# USB_SWITCH_B.net
KiCad netlist of a schematic drawn in Altium Designer
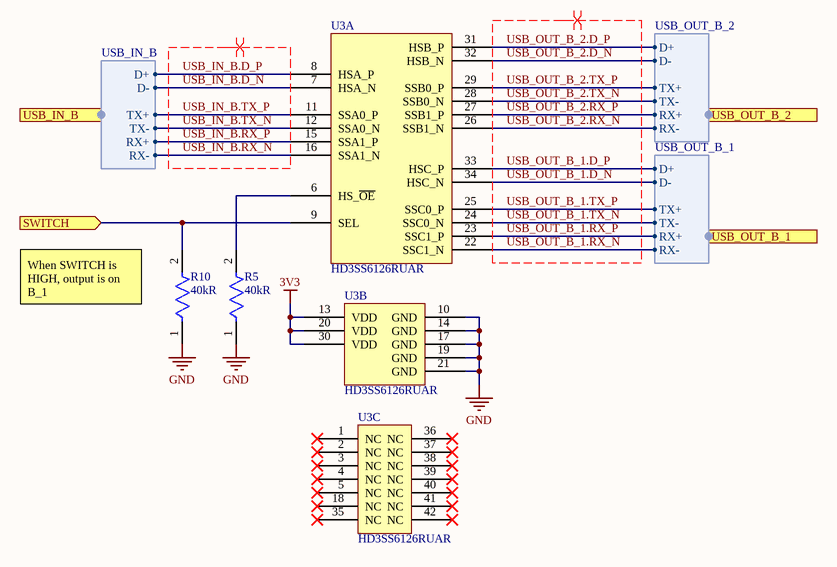
[diagram p0: USB_SWITCH_B.SchDoc]

(export (version "E")
  (design (tool "Eeschema 10.0.6"))
  (components
    (comp (ref "R5")
      (value "CRCW080540K0FKEA")
      (footprint "FP-CRCW0805-e3-MFG")
      (description "RES Thick Film, 40kΩ, 1%, 0.125W, 100ppm/°C, 0805")
      (fields (field (name "TOLERANCE") "1%") (field (name "RESISTANCE") "40kR"))
      (libsource (lib "Altium Content Vault") (part "1029c3af85768c4190bb7ad29bc67b5"))
    )
    (comp (ref "R10")
      (value "CRCW080540K0FKEA")
      (footprint "FP-CRCW0805-e3-MFG")
      (description "RES Thick Film, 40kΩ, 1%, 0.125W, 100ppm/°C, 0805")
      (fields (field (name "TOLERANCE") "1%") (field (name "RESISTANCE") "40kR"))
      (libsource (lib "Altium Content Vault") (part "1029c3af85768c4190bb7ad29bc67b5"))
    )
    (comp (ref "U3")
      (value "HD3SS6126RUAR")
      (footprint "QFN50P900X350X80-43N")
      (description "High Speed Differential Switch 2: 1/1: 2 MUX/DEMUX USB 2.0/USB 3.0 3.3V T/R 42-Pin WQFN EP")
      (libsource (lib "KVM Symbols") (part "HD3SS6126RUAR"))
    )
  )
  (nets
    (net (code "4") (name "/SWITCH") (class "Default")
      (node (ref "R10") (pin "2") (pinfunction "2_2") (pintype "passive"))
      (node (ref "U3") (pin "9") (pinfunction "SEL_9") (pintype "passive"))
    )
    (net (code "5") (name "/USB_IN_B.D_N") (class "Default")
      (node (ref "U3") (pin "7") (pinfunction "HSA_N_7") (pintype "passive"))
    )
    (net (code "6") (name "/USB_IN_B.D_P") (class "Default")
      (node (ref "U3") (pin "8") (pinfunction "HSA_P_8") (pintype "passive"))
    )
    (net (code "7") (name "/USB_IN_B.RX_N") (class "Default")
      (node (ref "U3") (pin "16") (pinfunction "SSA1_N_16") (pintype "passive"))
    )
    (net (code "8") (name "/USB_IN_B.RX_P") (class "Default")
      (node (ref "U3") (pin "15") (pinfunction "SSA1_P_15") (pintype "passive"))
    )
    (net (code "9") (name "/USB_IN_B.TX_N") (class "Default")
      (node (ref "U3") (pin "12") (pinfunction "SSA0_N_12") (pintype "passive"))
    )
    (net (code "10") (name "/USB_IN_B.TX_P") (class "Default")
      (node (ref "U3") (pin "11") (pinfunction "SSA0_P_11") (pintype "passive"))
    )
    (net (code "11") (name "/USB_OUT_B_1.D_N") (class "Default")
      (node (ref "U3") (pin "34") (pinfunction "HSC_N_34") (pintype "passive"))
    )
    (net (code "12") (name "/USB_OUT_B_1.D_P") (class "Default")
      (node (ref "U3") (pin "33") (pinfunction "HSC_P_33") (pintype "passive"))
    )
    (net (code "13") (name "/USB_OUT_B_1.RX_N") (class "Default")
      (node (ref "U3") (pin "22") (pinfunction "SSC1_N_22") (pintype "passive"))
    )
    (net (code "14") (name "/USB_OUT_B_1.RX_P") (class "Default")
      (node (ref "U3") (pin "23") (pinfunction "SSC1_P_23") (pintype "passive"))
    )
    (net (code "15") (name "/USB_OUT_B_1.TX_N") (class "Default")
      (node (ref "U3") (pin "24") (pinfunction "SSC0_N_24") (pintype "passive"))
    )
    (net (code "16") (name "/USB_OUT_B_1.TX_P") (class "Default")
      (node (ref "U3") (pin "25") (pinfunction "SSC0_P_25") (pintype "passive"))
    )
    (net (code "17") (name "/USB_OUT_B_2.D_N") (class "Default")
      (node (ref "U3") (pin "32") (pinfunction "HSB_N_32") (pintype "passive"))
    )
    (net (code "18") (name "/USB_OUT_B_2.D_P") (class "Default")
      (node (ref "U3") (pin "31") (pinfunction "HSB_P_31") (pintype "passive"))
    )
    (net (code "19") (name "/USB_OUT_B_2.RX_N") (class "Default")
      (node (ref "U3") (pin "26") (pinfunction "SSB1_N_26") (pintype "passive"))
    )
    (net (code "20") (name "/USB_OUT_B_2.RX_P") (class "Default")
      (node (ref "U3") (pin "27") (pinfunction "SSB1_P_27") (pintype "passive"))
    )
    (net (code "21") (name "/USB_OUT_B_2.TX_N") (class "Default")
      (node (ref "U3") (pin "28") (pinfunction "SSB0_N_28") (pintype "passive"))
    )
    (net (code "22") (name "/USB_OUT_B_2.TX_P") (class "Default")
      (node (ref "U3") (pin "29") (pinfunction "SSB0_P_29") (pintype "passive"))
    )
    (net (code "26") (name "3V3") (class "Default")
      (node (ref "U3") (pin "13") (pinfunction "VDD_13") (pintype "passive"))
      (node (ref "U3") (pin "20") (pinfunction "VDD_20") (pintype "passive"))
      (node (ref "U3") (pin "30") (pinfunction "VDD_30") (pintype "passive"))
    )
    (net (code "27") (name "GND") (class "Default")
      (node (ref "R10") (pin "1") (pinfunction "1_1") (pintype "passive"))
      (node (ref "R5") (pin "1") (pinfunction "1_1") (pintype "passive"))
      (node (ref "U3") (pin "10") (pinfunction "GND_10") (pintype "passive"))
      (node (ref "U3") (pin "14") (pinfunction "GND_14") (pintype "passive"))
      (node (ref "U3") (pin "17") (pinfunction "GND_17") (pintype "passive"))
      (node (ref "U3") (pin "19") (pinfunction "GND_19") (pintype "passive"))
      (node (ref "U3") (pin "21") (pinfunction "GND_21") (pintype "passive"))
    )
    (net (code "28") (name "Net-(U3A-HS_~{OE})") (class "Default")
      (node (ref "R5") (pin "2") (pinfunction "2_2") (pintype "passive"))
      (node (ref "U3") (pin "6") (pinfunction "HS_~{OE}_6") (pintype "passive"))
    )
    (net (code "29") (name "unconnected-(U3C-NC-Pad1)") (class "Default")
      (node (ref "U3") (pin "1") (pinfunction "NC_1") (pintype "passive+no_connect"))
    )
    (net (code "30") (name "unconnected-(U3C-NC-Pad2)") (class "Default")
      (node (ref "U3") (pin "2") (pinfunction "NC_2") (pintype "passive+no_connect"))
    )
    (net (code "31") (name "unconnected-(U3C-NC-Pad3)") (class "Default")
      (node (ref "U3") (pin "3") (pinfunction "NC_3") (pintype "passive+no_connect"))
    )
    (net (code "32") (name "unconnected-(U3C-NC-Pad4)") (class "Default")
      (node (ref "U3") (pin "4") (pinfunction "NC_4") (pintype "passive+no_connect"))
    )
    (net (code "33") (name "unconnected-(U3C-NC-Pad5)") (class "Default")
      (node (ref "U3") (pin "5") (pinfunction "NC_5") (pintype "passive+no_connect"))
    )
    (net (code "34") (name "unconnected-(U3C-NC-Pad18)") (class "Default")
      (node (ref "U3") (pin "18") (pinfunction "NC_18") (pintype "passive+no_connect"))
    )
    (net (code "35") (name "unconnected-(U3C-NC-Pad35)") (class "Default")
      (node (ref "U3") (pin "35") (pinfunction "NC_35") (pintype "passive+no_connect"))
    )
    (net (code "36") (name "unconnected-(U3C-NC-Pad36)") (class "Default")
      (node (ref "U3") (pin "36") (pinfunction "NC_36") (pintype "passive+no_connect"))
    )
    (net (code "37") (name "unconnected-(U3C-NC-Pad37)") (class "Default")
      (node (ref "U3") (pin "37") (pinfunction "NC_37") (pintype "passive+no_connect"))
    )
    (net (code "38") (name "unconnected-(U3C-NC-Pad38)") (class "Default")
      (node (ref "U3") (pin "38") (pinfunction "NC_38") (pintype "passive+no_connect"))
    )
    (net (code "39") (name "unconnected-(U3C-NC-Pad39)") (class "Default")
      (node (ref "U3") (pin "39") (pinfunction "NC_39") (pintype "passive+no_connect"))
    )
    (net (code "40") (name "unconnected-(U3C-NC-Pad40)") (class "Default")
      (node (ref "U3") (pin "40") (pinfunction "NC_40") (pintype "passive+no_connect"))
    )
    (net (code "41") (name "unconnected-(U3C-NC-Pad41)") (class "Default")
      (node (ref "U3") (pin "41") (pinfunction "NC_41") (pintype "passive+no_connect"))
    )
    (net (code "42") (name "unconnected-(U3C-NC-Pad42)") (class "Default")
      (node (ref "U3") (pin "42") (pinfunction "NC_42") (pintype "passive+no_connect"))
    )
  )
)
